# ROCKCHIP_SYSTEM_CONTROL.net
KiCad netlist of a schematic drawn in Altium Designer
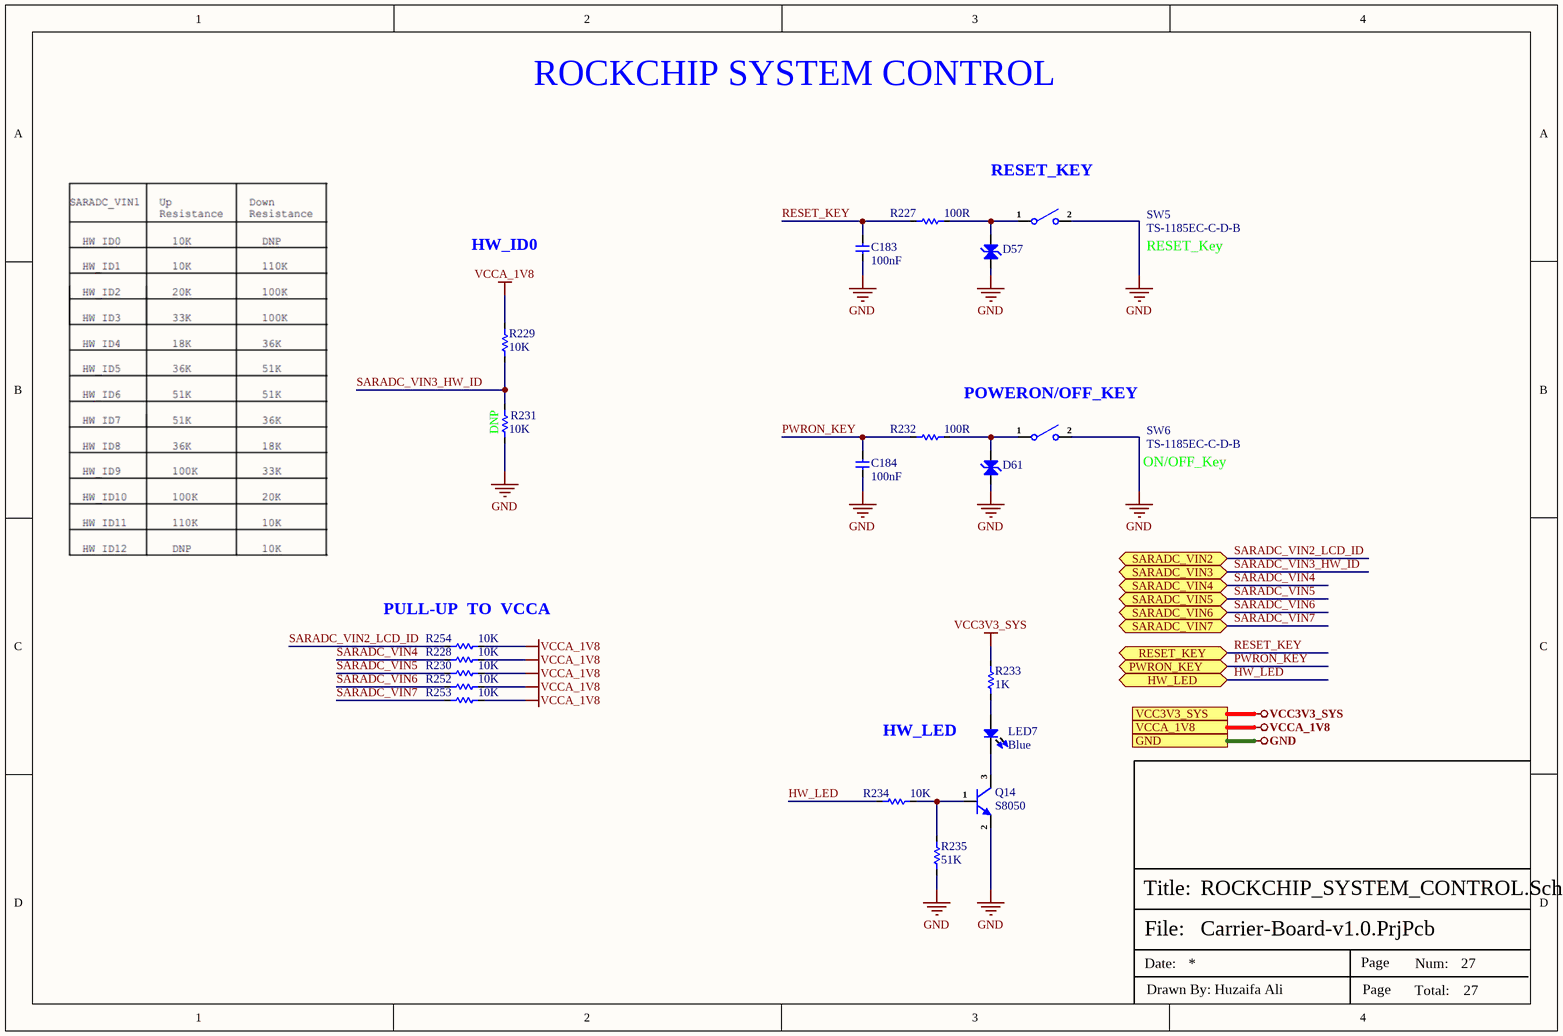
[diagram p0: ROCKCHIP_SYSTEM_CONTROL.SchDoc]

(export (version "E")
  (design (tool "Eeschema 10.0.6"))
  (components
    (comp (ref "C183")
      (value "100nF")
      (footprint "Cap-0402")
      (description "CAP CER 0.1UF 16V X5R 0402")
      (fields
        (field (name "MANUFACTURER") "Yageo")
        (field (name "MANUFACTURER PART NUMBER") "CC0402KRX5R7BB104")
      )
      (libsource (lib "eSpark Libraries") (part "CC0402KRX5R7BB104"))
    )
    (comp (ref "C184")
      (value "100nF")
      (footprint "Cap-0402")
      (description "CAP CER 0.1UF 16V X5R 0402")
      (fields
        (field (name "MANUFACTURER") "Yageo")
        (field (name "MANUFACTURER PART NUMBER") "CC0402KRX5R7BB104")
      )
      (libsource (lib "eSpark Libraries") (part "CC0402KRX5R7BB104"))
    )
    (comp (ref "D57")
      (value "ESD5451N")
      (footprint "DFN1006-2L (Bi-Directional)")
      (description "DFN1006-2(0402) ESD Protection Devices ROHS")
      (fields (field (name "MANUFACTURER") "TECH PUBLIC") (field (name "LCSC PART NUMBER") "C2936977"))
      (libsource (lib "eSpark Libraries") (part "ESD5451N"))
    )
    (comp (ref "D61")
      (value "ESD5451N")
      (footprint "DFN1006-2L (Bi-Directional)")
      (description "DFN1006-2(0402) ESD Protection Devices ROHS")
      (fields (field (name "MANUFACTURER") "TECH PUBLIC") (field (name "LCSC PART NUMBER") "C2936977"))
      (libsource (lib "eSpark Libraries") (part "ESD5451N"))
    )
    (comp (ref "LED7")
      (value "Blue")
      (footprint "LED-0402")
      (description "LED BLUE CLEAR 2SMD")
      (fields (field (name "MANUFACTURER") "SunLED") (field (name "MANUFACTURER PART NUMBER") "XZCBD68W-2"))
      (libsource (lib "eSpark Libraries") (part "XZCBD68W-2"))
    )
    (comp (ref "Q14")
      (value "S8050")
      (footprint "SOT-23")
      (description "Trans Gp Bjt NPN 25V 1.5A 300MW 3-PIN SOT-23 T/r")
      (fields (field (name "MANUFACTURER") "Comchip") (field (name "MANUFACTURER PART NUMBER") "SS8050-G"))
      (libsource (lib "eSpark Libraries") (part "S8050"))
    )
    (comp (ref "R227")
      (value "100R")
      (footprint "Res-0402")
      (description "RES 100 OHM 1% 1/16W 0402")
      (fields
        (field (name "MANUFACTURER") "Yageo")
        (field (name "MANUFACTURER PART NUMBER") "RC0402FR-07100RL")
      )
      (libsource (lib "eSpark Libraries") (part "RC0402FR-07100RL"))
    )
    (comp (ref "R228")
      (value "10K")
      (footprint "Res-0402")
      (description "RES 10K OHM 1% 1/16W 0402")
      (fields
        (field (name "MANUFACTURER") "Yageo")
        (field (name "MANUFACTURER PART NUMBER") "RC0402FR-0710KL")
      )
      (libsource (lib "eSpark Libraries") (part "RC0402FR-0710KL"))
    )
    (comp (ref "R229")
      (value "10K")
      (footprint "Res-0402")
      (description "RES 10K OHM 1% 1/16W 0402")
      (fields
        (field (name "MANUFACTURER") "Yageo")
        (field (name "MANUFACTURER PART NUMBER") "RC0402FR-0710KL")
      )
      (libsource (lib "eSpark Libraries") (part "RC0402FR-0710KL"))
    )
    (comp (ref "R230")
      (value "10K")
      (footprint "Res-0402")
      (description "RES 10K OHM 1% 1/16W 0402")
      (fields
        (field (name "MANUFACTURER") "Yageo")
        (field (name "MANUFACTURER PART NUMBER") "RC0402FR-0710KL")
      )
      (libsource (lib "eSpark Libraries") (part "RC0402FR-0710KL"))
    )
    (comp (ref "R231")
      (value "DNP")
      (footprint "Res-0402")
      (description "RES 10K OHM 1% 1/16W 0402")
      (fields
        (field (name "MANUFACTURER") "Yageo")
        (field (name "MANUFACTURER PART NUMBER") "RC0402FR-0710KL")
      )
      (libsource (lib "eSpark Libraries") (part "RC0402FR-0710KL"))
    )
    (comp (ref "R232")
      (value "100R")
      (footprint "Res-0402")
      (description "RES 100 OHM 1% 1/16W 0402")
      (fields
        (field (name "MANUFACTURER") "Yageo")
        (field (name "MANUFACTURER PART NUMBER") "RC0402FR-07100RL")
      )
      (libsource (lib "eSpark Libraries") (part "RC0402FR-07100RL"))
    )
    (comp (ref "R233")
      (value "1K")
      (footprint "Res-0603")
      (description "RES SMD 1K OHM 1% 1/10W 0603")
      (fields (field (name "LCSC PART NUMBER") "C844920") (field (name "MANUFACTURER") "Vishay Dale"))
      (libsource (lib "eSpark Libraries") (part "CRCW06031K00FKEA"))
    )
    (comp (ref "R234")
      (value "10K")
      (footprint "Res-0402")
      (description "RES 10K OHM 1% 1/16W 0402")
      (fields
        (field (name "MANUFACTURER") "Yageo")
        (field (name "MANUFACTURER PART NUMBER") "RC0402FR-0710KL")
      )
      (libsource (lib "eSpark Libraries") (part "RC0402FR-0710KL"))
    )
    (comp (ref "R235")
      (value "51K")
      (footprint "Res-0402")
      (description "RES 51K OHM 1% 1/16W 0402")
      (fields
        (field (name "MANUFACTURER") "Yageo")
        (field (name "MANUFACTURER PART NUMBER") "RC0402FR-0751KL")
      )
      (libsource (lib "eSpark Libraries") (part "RC0402FR-0751KL"))
    )
    (comp (ref "R252")
      (value "10K")
      (footprint "Res-0402")
      (description "RES 10K OHM 1% 1/16W 0402")
      (fields
        (field (name "MANUFACTURER") "Yageo")
        (field (name "MANUFACTURER PART NUMBER") "RC0402FR-0710KL")
      )
      (libsource (lib "eSpark Libraries") (part "RC0402FR-0710KL"))
    )
    (comp (ref "R253")
      (value "10K")
      (footprint "Res-0402")
      (description "RES 10K OHM 1% 1/16W 0402")
      (fields
        (field (name "MANUFACTURER") "Yageo")
        (field (name "MANUFACTURER PART NUMBER") "RC0402FR-0710KL")
      )
      (libsource (lib "eSpark Libraries") (part "RC0402FR-0710KL"))
    )
    (comp (ref "R254")
      (value "10K")
      (footprint "Res-0402")
      (description "RES 10K OHM 1% 1/16W 0402")
      (fields
        (field (name "MANUFACTURER") "Yageo")
        (field (name "MANUFACTURER PART NUMBER") "RC0402FR-0710KL")
      )
      (libsource (lib "eSpark Libraries") (part "RC0402FR-0710KL"))
    )
    (comp (ref "SW5")
      (value "TS-1185EC-C-D-B")
      (footprint "TS-1185EC-C-D-B_")
      (description "3mm 2mm Round Button 50mA Top3.65mm SPST 12V SMD Tactile Switches")
      (fields (field (name "MANUFACTURER") "XKB") (field (name "LCSC PART NUMBER") "C318893"))
      (libsource (lib "eSpark Libraries") (part "TS-1185EC-C-D-B"))
    )
    (comp (ref "SW6")
      (value "TS-1185EC-C-D-B")
      (footprint "TS-1185EC-C-D-B_")
      (description "3mm 2mm Round Button 50mA Top3.65mm SPST 12V SMD Tactile Switches")
      (fields (field (name "MANUFACTURER") "XKB") (field (name "LCSC PART NUMBER") "C318893"))
      (libsource (lib "eSpark Libraries") (part "TS-1185EC-C-D-B"))
    )
  )
  (nets
    (net (code "1") (name "/HW_LED") (class "Default")
      (node (ref "R234") (pin "1") (pinfunction "1_1") (pintype "passive"))
    )
    (net (code "2") (name "/PWRON_KEY") (class "Default")
      (node (ref "C184") (pin "2") (pinfunction "2_2") (pintype "passive"))
      (node (ref "R232") (pin "1") (pinfunction "1_1") (pintype "passive"))
    )
    (net (code "3") (name "/RESET_KEY") (class "Default")
      (node (ref "C183") (pin "2") (pinfunction "2_2") (pintype "passive"))
      (node (ref "R227") (pin "1") (pinfunction "1_1") (pintype "passive"))
    )
    (net (code "4") (name "/SARADC_VIN2_LCD_ID") (class "Default")
      (node (ref "R254") (pin "2") (pinfunction "2_2") (pintype "passive"))
    )
    (net (code "5") (name "/SARADC_VIN3_HW_ID") (class "Default")
      (node (ref "R229") (pin "2") (pinfunction "2_2") (pintype "passive"))
      (node (ref "R231") (pin "1") (pinfunction "1_1") (pintype "passive"))
    )
    (net (code "6") (name "/SARADC_VIN4") (class "Default")
      (node (ref "R228") (pin "2") (pinfunction "2_2") (pintype "passive"))
    )
    (net (code "7") (name "/SARADC_VIN5") (class "Default")
      (node (ref "R230") (pin "2") (pinfunction "2_2") (pintype "passive"))
    )
    (net (code "8") (name "/SARADC_VIN6") (class "Default")
      (node (ref "R252") (pin "2") (pinfunction "2_2") (pintype "passive"))
    )
    (net (code "9") (name "/SARADC_VIN7") (class "Default")
      (node (ref "R253") (pin "2") (pinfunction "2_2") (pintype "passive"))
    )
    (net (code "10") (name "GND") (class "Default")
      (node (ref "C183") (pin "1") (pinfunction "1_1") (pintype "passive"))
      (node (ref "C184") (pin "1") (pinfunction "1_1") (pintype "passive"))
      (node (ref "D57") (pin "1") (pinfunction "K_1") (pintype "passive"))
      (node (ref "D61") (pin "1") (pinfunction "K_1") (pintype "passive"))
      (node (ref "Q14") (pin "2") (pinfunction "E_2") (pintype "passive"))
      (node (ref "R231") (pin "2") (pinfunction "2_2") (pintype "passive"))
      (node (ref "R235") (pin "1") (pinfunction "1_1") (pintype "passive"))
      (node (ref "SW5") (pin "2") (pinfunction "2_2") (pintype "passive"))
      (node (ref "SW6") (pin "2") (pinfunction "2_2") (pintype "passive"))
    )
    (net (code "11") (name "Net-(D57-K-Pad2)") (class "Default")
      (node (ref "D57") (pin "2") (pinfunction "K_2") (pintype "passive"))
      (node (ref "R227") (pin "2") (pinfunction "2_2") (pintype "passive"))
      (node (ref "SW5") (pin "1") (pinfunction "1_1") (pintype "passive"))
    )
    (net (code "12") (name "Net-(D61-K-Pad2)") (class "Default")
      (node (ref "D61") (pin "2") (pinfunction "K_2") (pintype "passive"))
      (node (ref "R232") (pin "2") (pinfunction "2_2") (pintype "passive"))
      (node (ref "SW6") (pin "1") (pinfunction "1_1") (pintype "passive"))
    )
    (net (code "13") (name "Net-(LED7-Pad1)") (class "Default")
      (node (ref "LED7") (pin "1") (pinfunction "1_1") (pintype "passive"))
      (node (ref "R233") (pin "1") (pinfunction "1_1") (pintype "passive"))
    )
    (net (code "14") (name "Net-(Q14-B)") (class "Default")
      (node (ref "Q14") (pin "1") (pinfunction "B_1") (pintype "passive"))
      (node (ref "R234") (pin "2") (pinfunction "2_2") (pintype "passive"))
      (node (ref "R235") (pin "2") (pinfunction "2_2") (pintype "passive"))
    )
    (net (code "15") (name "Net-(Q14-C)") (class "Default")
      (node (ref "LED7") (pin "2") (pinfunction "2_2") (pintype "passive"))
      (node (ref "Q14") (pin "3") (pinfunction "C_3") (pintype "passive"))
    )
    (net (code "16") (name "VCC3V3_SYS") (class "Default")
      (node (ref "R233") (pin "2") (pinfunction "2_2") (pintype "passive"))
    )
    (net (code "17") (name "VCCA_1V8") (class "Default")
      (node (ref "R228") (pin "1") (pinfunction "1_1") (pintype "passive"))
      (node (ref "R229") (pin "1") (pinfunction "1_1") (pintype "passive"))
      (node (ref "R230") (pin "1") (pinfunction "1_1") (pintype "passive"))
      (node (ref "R252") (pin "1") (pinfunction "1_1") (pintype "passive"))
      (node (ref "R253") (pin "1") (pinfunction "1_1") (pintype "passive"))
      (node (ref "R254") (pin "1") (pinfunction "1_1") (pintype "passive"))
    )
  )
)
